# tps63020-buck-boost-flashlight-driver-17.net
KiCad netlist of a schematic drawn in EAGLE
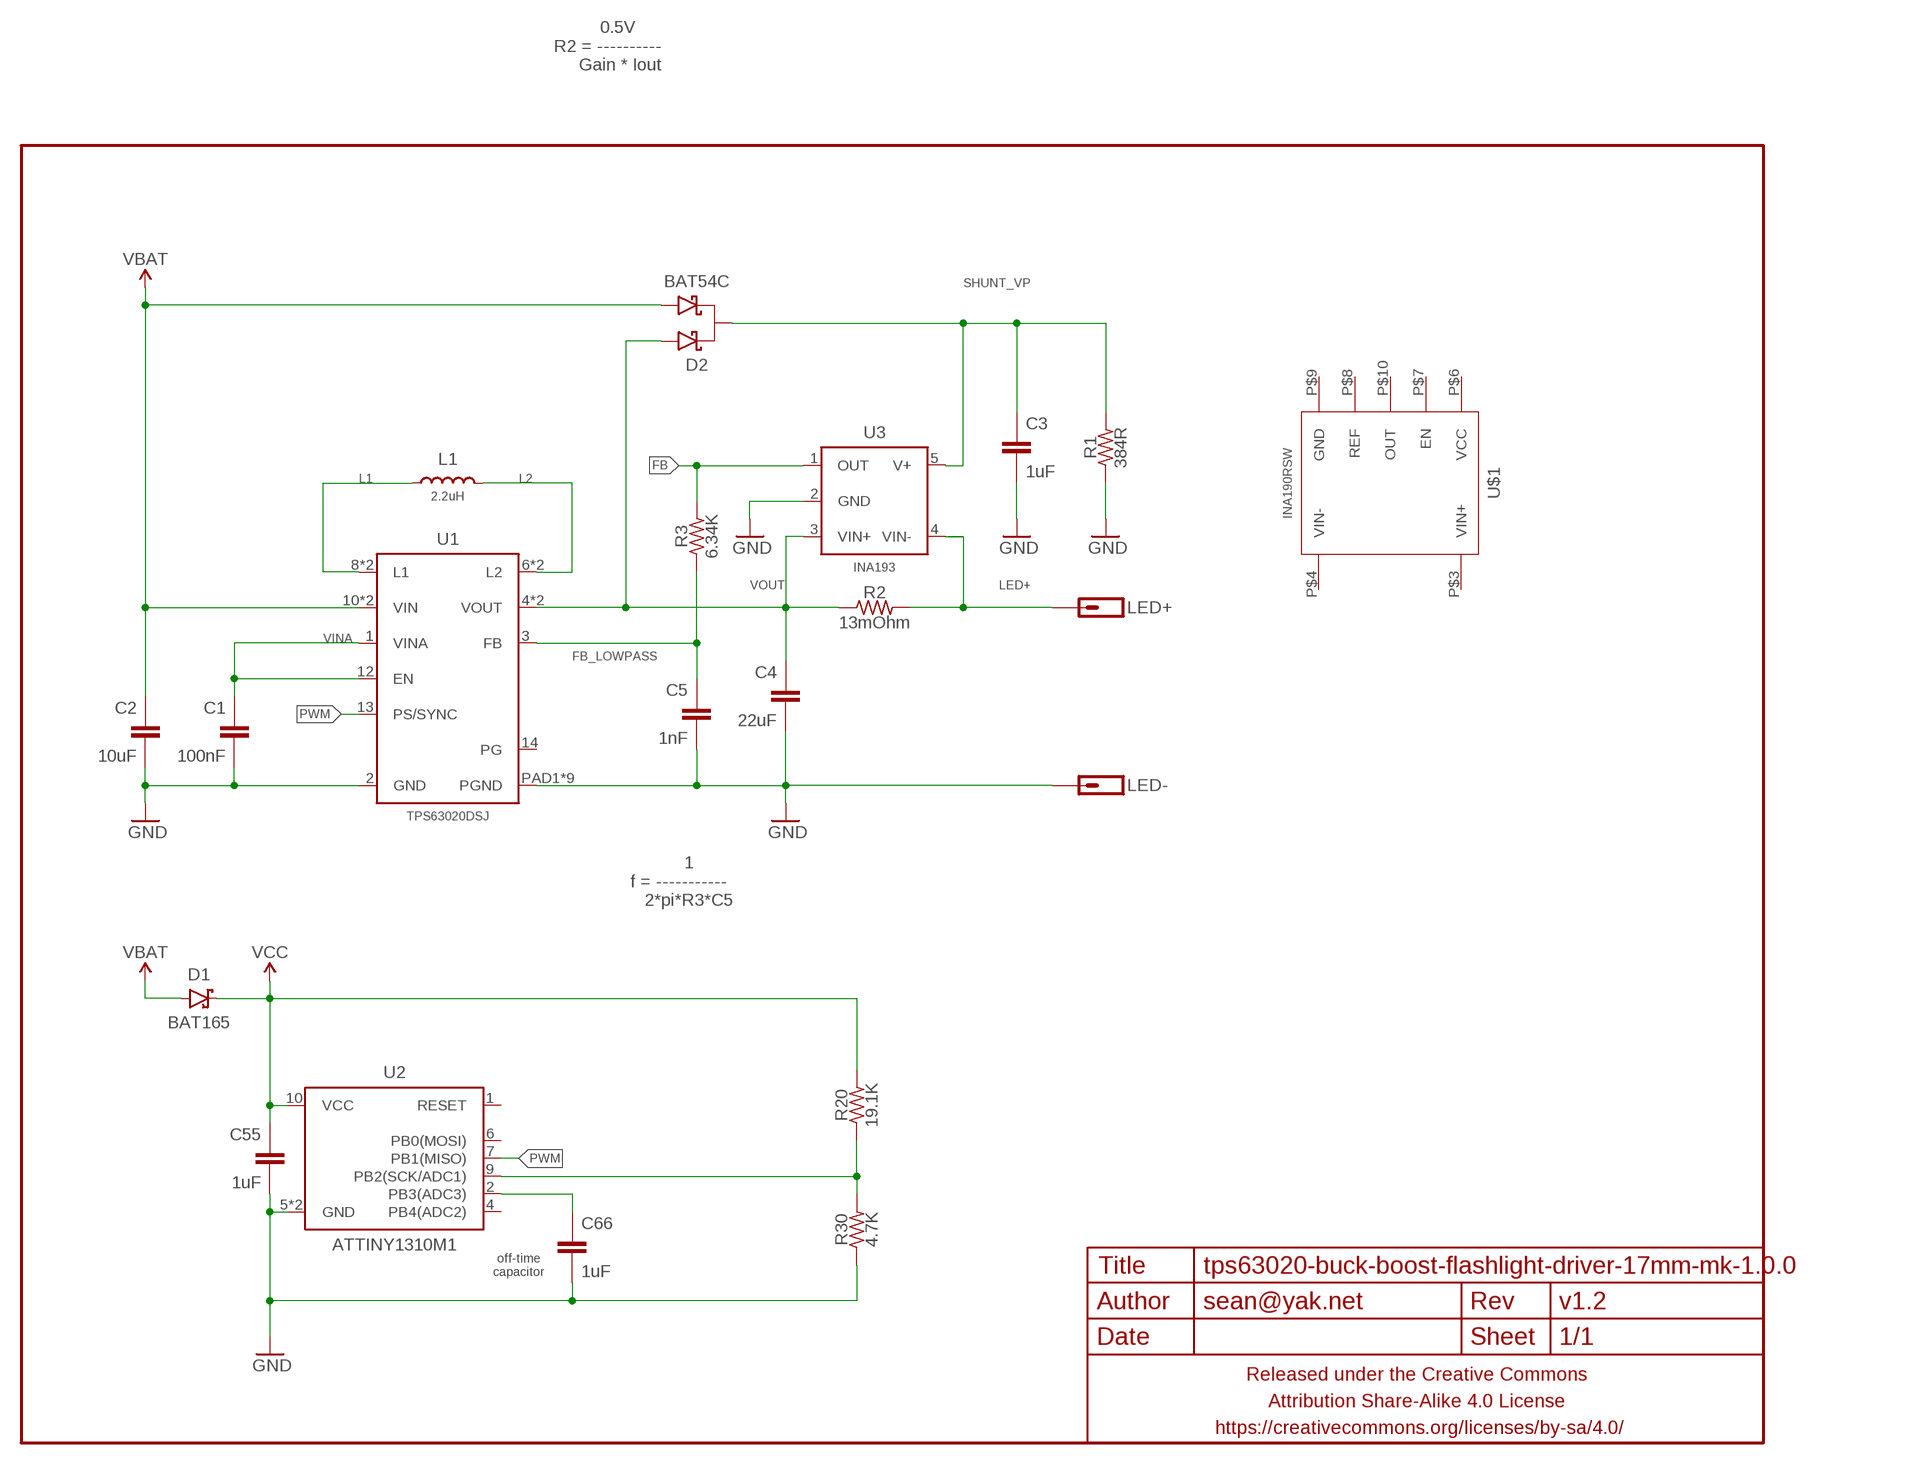
[diagram p0: schematic, sheet 1]

(export (version "E")
  (design (tool "Eeschema 10.0.6"))
  (components
    (comp (ref "C1")
      (value "100nF")
      (footprint "eagle-import:C0402")
      (libsource (lib "eagle-import") (part "CAPACITOR-CERAMICC0402"))
    )
    (comp (ref "C2")
      (value "10uF")
      (footprint "eagle-import:C0603-TIGHTER")
      (libsource (lib "eagle-import") (part "CAPACITOR-CERAMICC0603-TIGHTER"))
    )
    (comp (ref "C3")
      (value "1uF")
      (footprint "eagle-import:C0402")
      (libsource (lib "eagle-import") (part "CAPACITOR-CERAMICC0402"))
    )
    (comp (ref "C4")
      (value "22uF")
      (footprint "eagle-import:C0603-TIGHTER")
      (libsource (lib "eagle-import") (part "CAPACITOR-CERAMICC0603-TIGHTER"))
    )
    (comp (ref "C5")
      (value "1nF")
      (footprint "eagle-import:C0402")
      (libsource (lib "eagle-import") (part "CAPACITOR-CERAMICC0402"))
    )
    (comp (ref "C55")
      (value "1uF")
      (footprint "eagle-import:C0603-TIGHTER")
      (libsource (lib "eagle-import") (part "CAPACITOR-CERAMICC0603-TIGHTER"))
    )
    (comp (ref "C66")
      (value "1uF")
      (footprint "eagle-import:C0402")
      (libsource (lib "eagle-import") (part "CAPACITOR-CERAMICC0402"))
    )
    (comp (ref "D1")
      (value "BAT165")
      (footprint "eagle-import:SOD323-SCHOTTKY")
      (libsource (lib "eagle-import") (part "DIODE-SCHOTTKYSOD323"))
    )
    (comp (ref "D2")
      (value "BAT54C")
      (footprint "eagle-import:SOT23")
      (libsource (lib "eagle-import") (part "DIODE-SCHOTTKY-DUALBAT54C"))
    )
    (comp (ref "FRAME1")
      (value "FRAME-LETTERNO_PACKAGE")
      (footprint "eagle-import:DUMMY")
      (fields
        (field (name "DESIGNER") "Nobody")
        (field (name "VERSION") "v01")
        (field (name "DESIGNER_1") "sean@yak.net")
        (field (name "VERSION_1") "v1.2")
      )
      (libsource (lib "eagle-import") (part "FRAME-LETTERNO_PACKAGE"))
    )
    (comp (ref "L1")
      (value "2.2uH")
      (footprint "eagle-import:XAL50X0")
      (libsource (lib "eagle-import") (part "INDUCTORXAL50X0"))
    )
    (comp (ref "LED+")
      (value "M01PTH-1MM-CIR-NS")
      (footprint "eagle-import:1X01-1MM-CIR-NS")
      (libsource (lib "eagle-import") (part "M01PTH-1MM-CIR-NS"))
    )
    (comp (ref "LED-")
      (value "M01PTH-1MM-CIR-NS")
      (footprint "eagle-import:1X01-1MM-CIR-NS")
      (libsource (lib "eagle-import") (part "M01PTH-1MM-CIR-NS"))
    )
    (comp (ref "R1")
      (value "384R")
      (footprint "eagle-import:R0402")
      (libsource (lib "eagle-import") (part "RESISTORR0402"))
    )
    (comp (ref "R2")
      (value "13mOhm")
      (footprint "eagle-import:R0805-TIGHTER")
      (libsource (lib "eagle-import") (part "RESISTORR0805-TIGHTER"))
    )
    (comp (ref "R3")
      (value "6.34K")
      (footprint "eagle-import:R0402")
      (libsource (lib "eagle-import") (part "RESISTORR0402"))
    )
    (comp (ref "R20")
      (value "19.1K")
      (footprint "eagle-import:R0603-TIGHTER")
      (libsource (lib "eagle-import") (part "RESISTORR0603-TIGHTER"))
    )
    (comp (ref "R30")
      (value "4.7K")
      (footprint "eagle-import:R0603-TIGHTER")
      (libsource (lib "eagle-import") (part "RESISTORR0603-TIGHTER"))
    )
    (comp (ref "U$1")
      (value "INA190RSW")
      (footprint "eagle-import:UQFN-10")
      (libsource (lib "eagle-import") (part "INA190RSW"))
    )
    (comp (ref "U1")
      (value "TPS63020DSJ")
      (footprint "eagle-import:VSON-14-4MMX3MM")
      (libsource (lib "eagle-import") (part "TPS63020DSJ"))
    )
    (comp (ref "U2")
      (value "ATTINY1310M1")
      (footprint "eagle-import:QFN10(2X5)")
      (libsource (lib "eagle-import") (part "ATTINY1310M1"))
    )
    (comp (ref "U3")
      (value "INA193")
      (footprint "eagle-import:SOT23-5")
      (libsource (lib "eagle-import") (part "INA193"))
    )
  )
  (nets
    (net (code "1") (name "/FB_LOWPASS") (class "Default")
      (node (ref "C5") (pin "1") (pinfunction "1_1") (pintype "passive"))
      (node (ref "R3") (pin "1") (pinfunction "1_1") (pintype "passive"))
      (node (ref "U1") (pin "3") (pinfunction "FB_3") (pintype "bidirectional"))
    )
    (net (code "2") (name "/L1") (class "Default")
      (node (ref "L1") (pin "P$1") (pinfunction "1_P$1") (pintype "passive"))
      (node (ref "U1") (pin "8") (pinfunction "L1_8") (pintype "bidirectional"))
      (node (ref "U1") (pin "9") (pinfunction "L1_9") (pintype "bidirectional"))
    )
    (net (code "3") (name "/L2") (class "Default")
      (node (ref "L1") (pin "P$2") (pinfunction "2_P$2") (pintype "passive"))
      (node (ref "U1") (pin "6") (pinfunction "L2_6") (pintype "bidirectional"))
      (node (ref "U1") (pin "7") (pinfunction "L2_7") (pintype "bidirectional"))
    )
    (net (code "4") (name "/LED+") (class "Default")
      (node (ref "LED+") (pin "1") (pinfunction "1_1") (pintype "passive"))
      (node (ref "R2") (pin "2") (pinfunction "2_2") (pintype "passive"))
      (node (ref "U3") (pin "4") (pinfunction "VIN-_4") (pintype "bidirectional"))
    )
    (net (code "5") (name "/SHUNT_VP") (class "Default")
      (node (ref "C3") (pin "1") (pinfunction "1_1") (pintype "passive"))
      (node (ref "D2") (pin "3") (pinfunction "K_3") (pintype "passive"))
      (node (ref "R1") (pin "2") (pinfunction "2_2") (pintype "passive"))
      (node (ref "U3") (pin "5") (pinfunction "V+_5") (pintype "bidirectional"))
    )
    (net (code "6") (name "/VINA") (class "Default")
      (node (ref "C1") (pin "1") (pinfunction "1_1") (pintype "passive"))
      (node (ref "U1") (pin "1") (pinfunction "VINA_1") (pintype "bidirectional"))
      (node (ref "U1") (pin "12") (pinfunction "EN_12") (pintype "bidirectional"))
    )
    (net (code "7") (name "/VOUT") (class "Default")
      (node (ref "C4") (pin "1") (pinfunction "1_1") (pintype "passive"))
      (node (ref "D2") (pin "1") (pinfunction "A1_1") (pintype "passive"))
      (node (ref "R2") (pin "1") (pinfunction "1_1") (pintype "passive"))
      (node (ref "U1") (pin "4") (pinfunction "VOUT_4") (pintype "bidirectional"))
      (node (ref "U1") (pin "5") (pinfunction "VOUT_5") (pintype "bidirectional"))
      (node (ref "U3") (pin "3") (pinfunction "VIN+_3") (pintype "bidirectional"))
    )
    (net (code "8") (name "FB") (class "Default")
      (node (ref "R3") (pin "2") (pinfunction "2_2") (pintype "passive"))
      (node (ref "U3") (pin "1") (pinfunction "OUT_1") (pintype "bidirectional"))
    )
    (net (code "9") (name "GND") (class "Default")
      (node (ref "C1") (pin "2") (pinfunction "2_2") (pintype "passive"))
      (node (ref "C2") (pin "2") (pinfunction "2_2") (pintype "passive"))
      (node (ref "C3") (pin "2") (pinfunction "2_2") (pintype "passive"))
      (node (ref "C4") (pin "2") (pinfunction "2_2") (pintype "passive"))
      (node (ref "C5") (pin "2") (pinfunction "2_2") (pintype "passive"))
      (node (ref "C55") (pin "2") (pinfunction "2_2") (pintype "passive"))
      (node (ref "C66") (pin "2") (pinfunction "2_2") (pintype "passive"))
      (node (ref "LED-") (pin "1") (pinfunction "1_1") (pintype "passive"))
      (node (ref "R1") (pin "1") (pinfunction "1_1") (pintype "passive"))
      (node (ref "R30") (pin "1") (pinfunction "1_1") (pintype "passive"))
      (node (ref "U1") (pin "2") (pinfunction "GND_2") (pintype "bidirectional"))
      (node (ref "U1") (pin "PAD1") (pinfunction "PGND_PAD1") (pintype "bidirectional"))
      (node (ref "U1") (pin "PAD2") (pinfunction "PGND_PAD2") (pintype "bidirectional"))
      (node (ref "U1") (pin "PAD3") (pinfunction "PGND_PAD3") (pintype "bidirectional"))
      (node (ref "U1") (pin "PAD4") (pinfunction "PGND_PAD4") (pintype "bidirectional"))
      (node (ref "U1") (pin "PAD5") (pinfunction "PGND_PAD5") (pintype "bidirectional"))
      (node (ref "U1") (pin "PAD6") (pinfunction "PGND_PAD6") (pintype "bidirectional"))
      (node (ref "U1") (pin "PAD7") (pinfunction "PGND_PAD7") (pintype "bidirectional"))
      (node (ref "U1") (pin "PAD8") (pinfunction "PGND_PAD8") (pintype "bidirectional"))
      (node (ref "U1") (pin "PADCENTER") (pinfunction "PGND_PADCENTER") (pintype "bidirectional"))
      (node (ref "U2") (pin "5") (pinfunction "GND_5") (pintype "bidirectional"))
      (node (ref "U2") (pin "PAD") (pinfunction "GND_PAD") (pintype "bidirectional"))
      (node (ref "U3") (pin "2") (pinfunction "GND_2") (pintype "bidirectional"))
    )
    (net (code "10") (name "Net-(U2-PB2(SCK{slash}ADC1))") (class "Default")
      (node (ref "R20") (pin "1") (pinfunction "1_1") (pintype "passive"))
      (node (ref "R30") (pin "2") (pinfunction "2_2") (pintype "passive"))
      (node (ref "U2") (pin "9") (pinfunction "PB2(SCK/ADC1)_9") (pintype "bidirectional"))
    )
    (net (code "11") (name "Net-(U2-PB3(ADC3))") (class "Default")
      (node (ref "C66") (pin "1") (pinfunction "1_1") (pintype "passive"))
      (node (ref "U2") (pin "2") (pinfunction "PB3(ADC3)_2") (pintype "bidirectional"))
    )
    (net (code "12") (name "PWM") (class "Default")
      (node (ref "U1") (pin "13") (pinfunction "PS/SYNC_13") (pintype "bidirectional"))
      (node (ref "U2") (pin "7") (pinfunction "PB1(MISO)_7") (pintype "bidirectional"))
    )
    (net (code "13") (name "VBAT") (class "Default")
      (node (ref "C2") (pin "1") (pinfunction "1_1") (pintype "passive"))
      (node (ref "D1") (pin "A") (pinfunction "A_A") (pintype "passive"))
      (node (ref "D2") (pin "2") (pinfunction "A2_2") (pintype "passive"))
      (node (ref "U1") (pin "10") (pinfunction "VIN_10") (pintype "bidirectional"))
      (node (ref "U1") (pin "11") (pinfunction "VIN_11") (pintype "bidirectional"))
    )
    (net (code "14") (name "VCC") (class "Default")
      (node (ref "C55") (pin "1") (pinfunction "1_1") (pintype "passive"))
      (node (ref "D1") (pin "C") (pinfunction "C_C") (pintype "passive"))
      (node (ref "R20") (pin "2") (pinfunction "2_2") (pintype "passive"))
      (node (ref "U2") (pin "10") (pinfunction "VCC_10") (pintype "bidirectional"))
    )
    (net (code "15") (name "unconnected-(U$1-EN-PadP$7)") (class "Default")
      (node (ref "U$1") (pin "P$7") (pinfunction "EN_P$7") (pintype "bidirectional"))
    )
    (net (code "16") (name "unconnected-(U$1-GND-PadP$9)") (class "Default")
      (node (ref "U$1") (pin "P$9") (pinfunction "GND_P$9") (pintype "bidirectional"))
    )
    (net (code "17") (name "unconnected-(U$1-OUT-PadP$10)") (class "Default")
      (node (ref "U$1") (pin "P$10") (pinfunction "OUT_P$10") (pintype "bidirectional"))
    )
    (net (code "18") (name "unconnected-(U$1-REF-PadP$8)") (class "Default")
      (node (ref "U$1") (pin "P$8") (pinfunction "REF_P$8") (pintype "bidirectional"))
    )
    (net (code "19") (name "unconnected-(U$1-VCC-PadP$6)") (class "Default")
      (node (ref "U$1") (pin "P$6") (pinfunction "VCC_P$6") (pintype "bidirectional"))
    )
    (net (code "20") (name "unconnected-(U$1-VIN+-PadP$3)") (class "Default")
      (node (ref "U$1") (pin "P$3") (pinfunction "VIN+_P$3") (pintype "bidirectional"))
    )
    (net (code "21") (name "unconnected-(U$1-VIN--PadP$4)") (class "Default")
      (node (ref "U$1") (pin "P$4") (pinfunction "VIN-_P$4") (pintype "bidirectional"))
    )
    (net (code "22") (name "unconnected-(U1-PG-Pad14)") (class "Default")
      (node (ref "U1") (pin "14") (pinfunction "PG_14") (pintype "bidirectional"))
    )
    (net (code "23") (name "unconnected-(U2-PB0(MOSI)-Pad6)") (class "Default")
      (node (ref "U2") (pin "6") (pinfunction "PB0(MOSI)_6") (pintype "bidirectional"))
    )
    (net (code "24") (name "unconnected-(U2-PB4(ADC2)-Pad4)") (class "Default")
      (node (ref "U2") (pin "4") (pinfunction "PB4(ADC2)_4") (pintype "bidirectional"))
    )
    (net (code "25") (name "unconnected-(U2-RESET-Pad1)") (class "Default")
      (node (ref "U2") (pin "1") (pinfunction "RESET_1") (pintype "bidirectional"))
    )
  )
)
